# vga-wing.net
KiCad netlist of a schematic drawn in Altium Designer
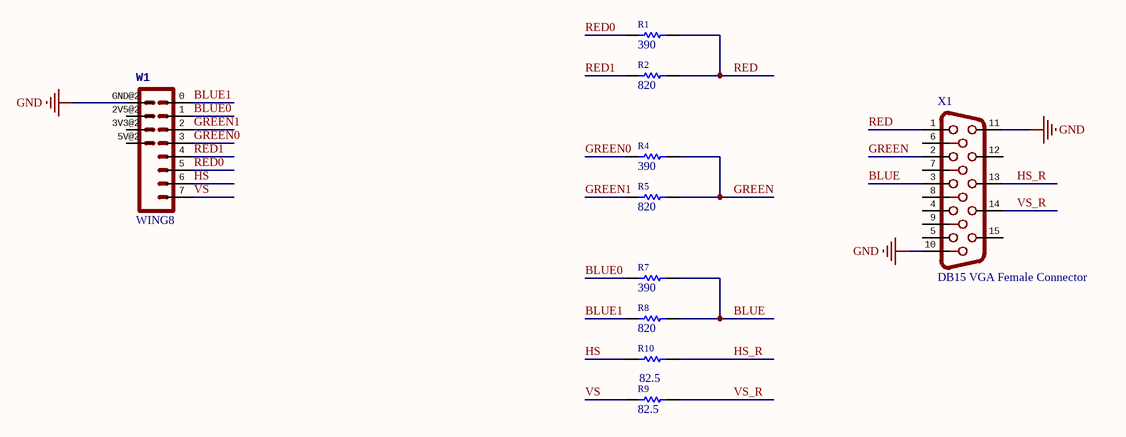
[diagram p0: vga-wing.SchDoc]

(export (version "E")
  (design (tool "Eeschema 10.0.6"))
  (components
    (comp (ref "R1")
      (value "390")
      (footprint "R0805_M")
      (description "Chip Resistor size 0805")
      (libsource (lib "MH - RCLDSX") (part "R0805"))
    )
    (comp (ref "R2")
      (value "820")
      (footprint "R0805_M")
      (description "Chip Resistor size 0805")
      (libsource (lib "MH - RCLDSX") (part "R0805"))
    )
    (comp (ref "R4")
      (value "390")
      (footprint "R0805_M")
      (description "Chip Resistor size 0805")
      (libsource (lib "MH - RCLDSX") (part "R0805"))
    )
    (comp (ref "R5")
      (value "820")
      (footprint "R0805_M")
      (description "Chip Resistor size 0805")
      (libsource (lib "MH - RCLDSX") (part "R0805"))
    )
    (comp (ref "R7")
      (value "390")
      (footprint "R0805_M")
      (description "Chip Resistor size 0805")
      (libsource (lib "MH - RCLDSX") (part "R0805"))
    )
    (comp (ref "R8")
      (value "820")
      (footprint "R0805_M")
      (description "Chip Resistor size 0805")
      (libsource (lib "MH - RCLDSX") (part "R0805"))
    )
    (comp (ref "R9")
      (value "82.5")
      (footprint "R0805_M")
      (description "Chip Resistor size 0805")
      (libsource (lib "MH - RCLDSX") (part "R0805"))
    )
    (comp (ref "R10")
      (value "82.5")
      (footprint "R0805_M")
      (description "Chip Resistor size 0805")
      (libsource (lib "MH - RCLDSX") (part "R0805"))
    )
    (comp (ref "W1") (value "WING8") (footprint "WINGSIDE_8BIT") (libsource (lib "Papilio") (part "WING8")))
    (comp (ref "X1")
      (value "DB15 VGA Female Connector")
      (footprint "HDF15H")
      (libsource (lib "vga") (part "HF15H"))
    )
  )
  (nets
    (net (code "1") (name "/BLUE") (class "Default")
      (node (ref "R7") (pin "1") (pinfunction "1_1") (pintype "passive"))
      (node (ref "R8") (pin "1") (pinfunction "1_1") (pintype "passive"))
      (node (ref "X1") (pin "3") (pinfunction "3_3") (pintype "passive"))
    )
    (net (code "2") (name "/BLUE0") (class "Default")
      (node (ref "R7") (pin "2") (pinfunction "2_2") (pintype "passive"))
      (node (ref "W1") (pin "1") (pinfunction "2_1") (pintype "passive"))
    )
    (net (code "3") (name "/BLUE1") (class "Default")
      (node (ref "R8") (pin "2") (pinfunction "2_2") (pintype "passive"))
      (node (ref "W1") (pin "0") (pinfunction "1_0") (pintype "passive"))
    )
    (net (code "4") (name "/GREEN") (class "Default")
      (node (ref "R4") (pin "1") (pinfunction "1_1") (pintype "passive"))
      (node (ref "R5") (pin "1") (pinfunction "1_1") (pintype "passive"))
      (node (ref "X1") (pin "2") (pinfunction "2_2") (pintype "passive"))
    )
    (net (code "5") (name "/GREEN0") (class "Default")
      (node (ref "R4") (pin "2") (pinfunction "2_2") (pintype "passive"))
      (node (ref "W1") (pin "3") (pinfunction "4_3") (pintype "passive"))
    )
    (net (code "6") (name "/GREEN1") (class "Default")
      (node (ref "R5") (pin "2") (pinfunction "2_2") (pintype "passive"))
      (node (ref "W1") (pin "2") (pinfunction "3_2") (pintype "passive"))
    )
    (net (code "7") (name "/HS") (class "Default")
      (node (ref "R10") (pin "2") (pinfunction "2_2") (pintype "passive"))
      (node (ref "W1") (pin "6") (pinfunction "7_6") (pintype "passive"))
    )
    (net (code "8") (name "/HS_R") (class "Default")
      (node (ref "R10") (pin "1") (pinfunction "1_1") (pintype "passive"))
      (node (ref "X1") (pin "13") (pinfunction "13_13") (pintype "passive"))
    )
    (net (code "9") (name "/RED") (class "Default")
      (node (ref "R1") (pin "1") (pinfunction "1_1") (pintype "passive"))
      (node (ref "R2") (pin "1") (pinfunction "1_1") (pintype "passive"))
      (node (ref "X1") (pin "1") (pinfunction "1_1") (pintype "passive"))
    )
    (net (code "10") (name "/RED0") (class "Default")
      (node (ref "R1") (pin "2") (pinfunction "2_2") (pintype "passive"))
      (node (ref "W1") (pin "5") (pinfunction "6_5") (pintype "passive"))
    )
    (net (code "11") (name "/RED1") (class "Default")
      (node (ref "R2") (pin "2") (pinfunction "2_2") (pintype "passive"))
      (node (ref "W1") (pin "4") (pinfunction "5_4") (pintype "passive"))
    )
    (net (code "12") (name "/VS") (class "Default")
      (node (ref "R9") (pin "2") (pinfunction "2_2") (pintype "passive"))
      (node (ref "W1") (pin "7") (pinfunction "8_7") (pintype "passive"))
    )
    (net (code "13") (name "/VS_R") (class "Default")
      (node (ref "R9") (pin "1") (pinfunction "1_1") (pintype "passive"))
      (node (ref "X1") (pin "14") (pinfunction "14_14") (pintype "passive"))
    )
    (net (code "14") (name "GND") (class "Default")
      (node (ref "W1") (pin "GND@2") (pinfunction "GND_GND@2") (pintype "passive"))
      (node (ref "X1") (pin "10") (pinfunction "10_10") (pintype "passive"))
      (node (ref "X1") (pin "11") (pinfunction "11_11") (pintype "passive"))
    )
    (net (code "15") (name "unconnected-(W1-2V5-Pad2V5@2)") (class "Default")
      (node (ref "W1") (pin "2V5@2") (pinfunction "2V5_2V5@2") (pintype "passive"))
    )
    (net (code "16") (name "unconnected-(W1-3V3-Pad3V3@2)") (class "Default")
      (node (ref "W1") (pin "3V3@2") (pinfunction "3V3_3V3@2") (pintype "passive"))
    )
    (net (code "17") (name "unconnected-(W1-5V-Pad5V@2)") (class "Default")
      (node (ref "W1") (pin "5V@2") (pinfunction "5V_5V@2") (pintype "passive"))
    )
    (net (code "18") (name "unconnected-(X1-Pad4)") (class "Default")
      (node (ref "X1") (pin "4") (pinfunction "4_4") (pintype "passive"))
    )
    (net (code "19") (name "unconnected-(X1-Pad5)") (class "Default")
      (node (ref "X1") (pin "5") (pinfunction "5_5") (pintype "passive"))
    )
    (net (code "20") (name "unconnected-(X1-Pad6)") (class "Default")
      (node (ref "X1") (pin "6") (pinfunction "6_6") (pintype "passive"))
    )
    (net (code "21") (name "unconnected-(X1-Pad7)") (class "Default")
      (node (ref "X1") (pin "7") (pinfunction "7_7") (pintype "passive"))
    )
    (net (code "22") (name "unconnected-(X1-Pad8)") (class "Default")
      (node (ref "X1") (pin "8") (pinfunction "8_8") (pintype "passive"))
    )
    (net (code "23") (name "unconnected-(X1-Pad9)") (class "Default")
      (node (ref "X1") (pin "9") (pinfunction "9_9") (pintype "passive"))
    )
    (net (code "24") (name "unconnected-(X1-Pad12)") (class "Default")
      (node (ref "X1") (pin "12") (pinfunction "12_12") (pintype "passive"))
    )
    (net (code "25") (name "unconnected-(X1-Pad15)") (class "Default")
      (node (ref "X1") (pin "15") (pinfunction "15_15") (pintype "passive"))
    )
  )
)
